# v2_pogo.net
KiCad netlist of a schematic drawn in EAGLE
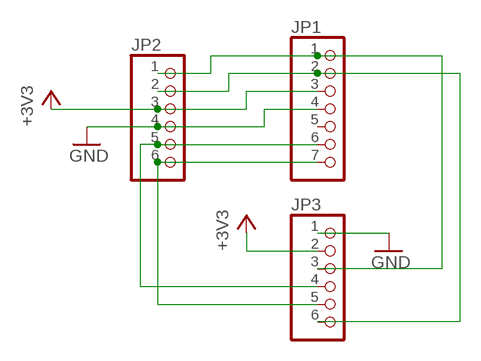
[diagram p0: schematic, sheet 1]

(export (version "E")
  (design (tool "Eeschema 10.0.6"))
  (components
    (comp (ref "JP1")
      (value "PINHD-1X7")
      (footprint "eagle-import:1X07")
      (libsource (lib "eagle-import") (part "PINHD-1X7"))
    )
    (comp (ref "JP2")
      (value "PINHD-1X6")
      (footprint "eagle-import:1X06")
      (libsource (lib "eagle-import") (part "PINHD-1X6"))
    )
    (comp (ref "JP3")
      (value "PINHD-1X6")
      (footprint "eagle-import:1X06")
      (libsource (lib "eagle-import") (part "PINHD-1X6"))
    )
  )
  (nets
    (net (code "1") (name "+3V3") (class "Default")
      (node (ref "JP1") (pin "3") (pinfunction "3_3") (pintype "passive"))
      (node (ref "JP2") (pin "3") (pinfunction "3_3") (pintype "passive"))
      (node (ref "JP3") (pin "2") (pinfunction "2_2") (pintype "passive"))
    )
    (net (code "2") (name "GND") (class "Default")
      (node (ref "JP1") (pin "4") (pinfunction "4_4") (pintype "passive"))
      (node (ref "JP2") (pin "4") (pinfunction "4_4") (pintype "passive"))
      (node (ref "JP3") (pin "1") (pinfunction "1_1") (pintype "passive"))
    )
    (net (code "3") (name "Net-(JP1-Pad1)") (class "Default")
      (node (ref "JP1") (pin "1") (pinfunction "1_1") (pintype "passive"))
      (node (ref "JP2") (pin "1") (pinfunction "1_1") (pintype "passive"))
      (node (ref "JP3") (pin "3") (pinfunction "3_3") (pintype "passive"))
    )
    (net (code "4") (name "Net-(JP1-Pad2)") (class "Default")
      (node (ref "JP1") (pin "2") (pinfunction "2_2") (pintype "passive"))
      (node (ref "JP2") (pin "2") (pinfunction "2_2") (pintype "passive"))
      (node (ref "JP3") (pin "6") (pinfunction "6_6") (pintype "passive"))
    )
    (net (code "5") (name "Net-(JP1-Pad6)") (class "Default")
      (node (ref "JP1") (pin "6") (pinfunction "6_6") (pintype "passive"))
      (node (ref "JP2") (pin "5") (pinfunction "5_5") (pintype "passive"))
      (node (ref "JP3") (pin "4") (pinfunction "4_4") (pintype "passive"))
    )
    (net (code "6") (name "Net-(JP1-Pad7)") (class "Default")
      (node (ref "JP1") (pin "7") (pinfunction "7_7") (pintype "passive"))
      (node (ref "JP2") (pin "6") (pinfunction "6_6") (pintype "passive"))
      (node (ref "JP3") (pin "5") (pinfunction "5_5") (pintype "passive"))
    )
    (net (code "7") (name "unconnected-(JP1-Pad5)") (class "Default")
      (node (ref "JP1") (pin "5") (pinfunction "5_5") (pintype "passive"))
    )
  )
)
